# 0152_HPB_BATTERY_CHARGE.net
KiCad netlist of a schematic drawn in Altium Designer
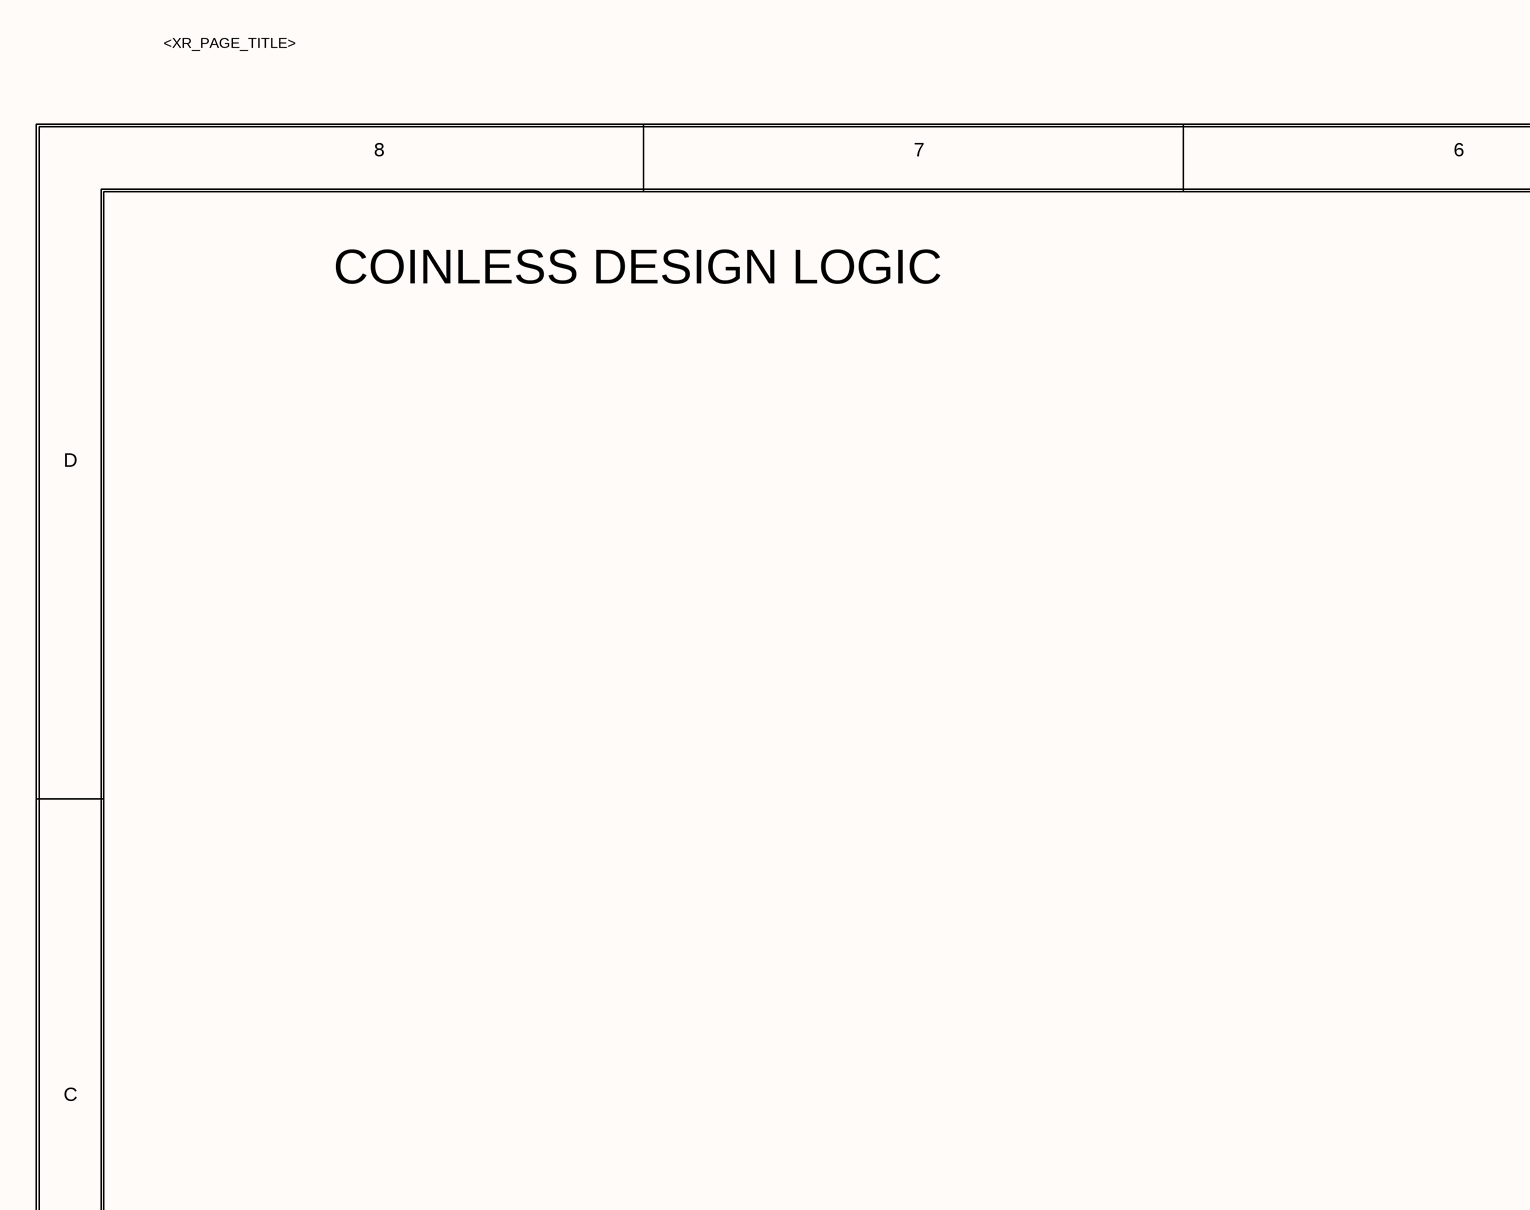
[diagram p0: 0152_HPB BATTERY CHARGE.SchDoc, top left]
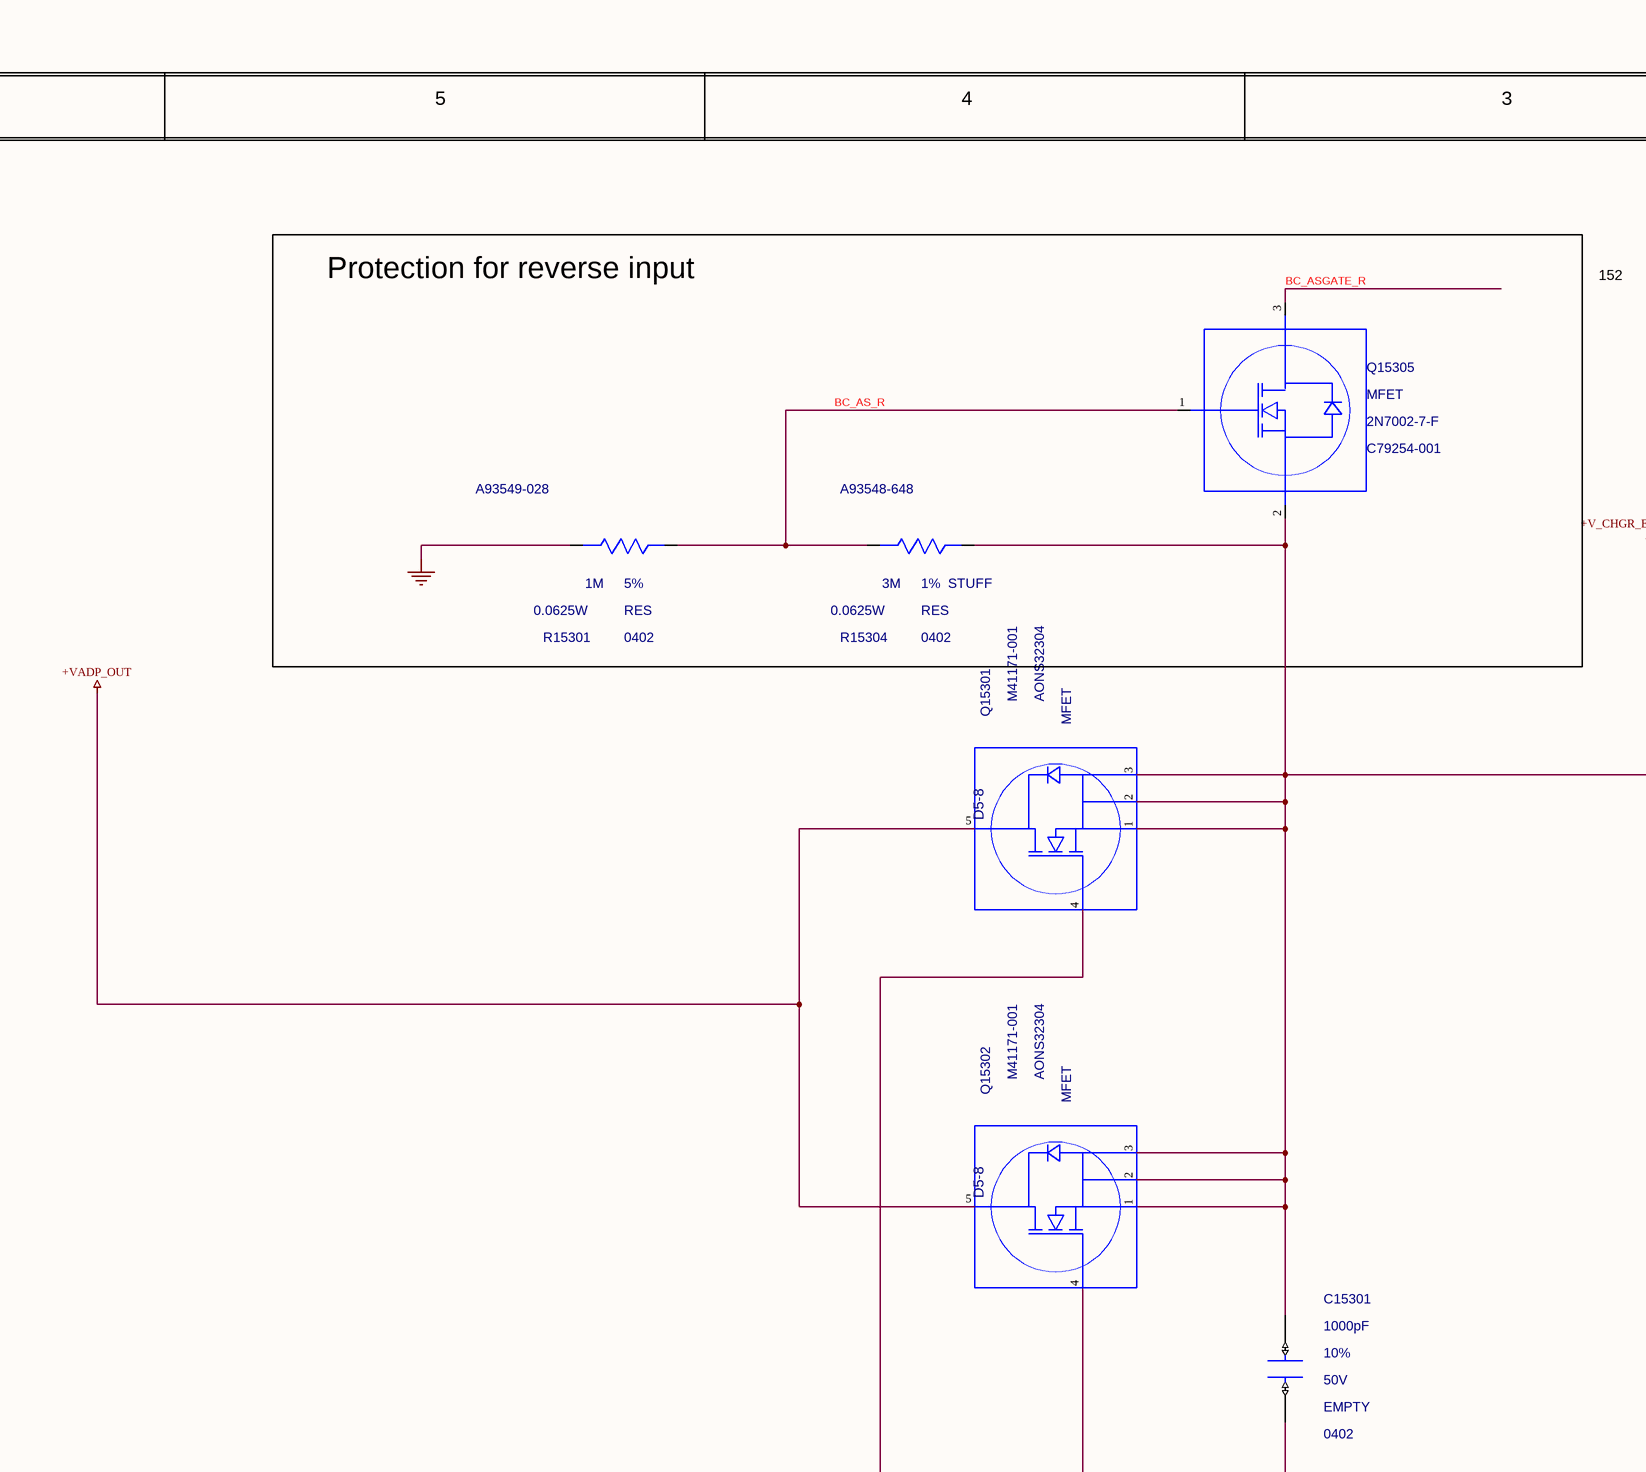
[diagram p1: 0152_HPB BATTERY CHARGE.SchDoc, top middle]
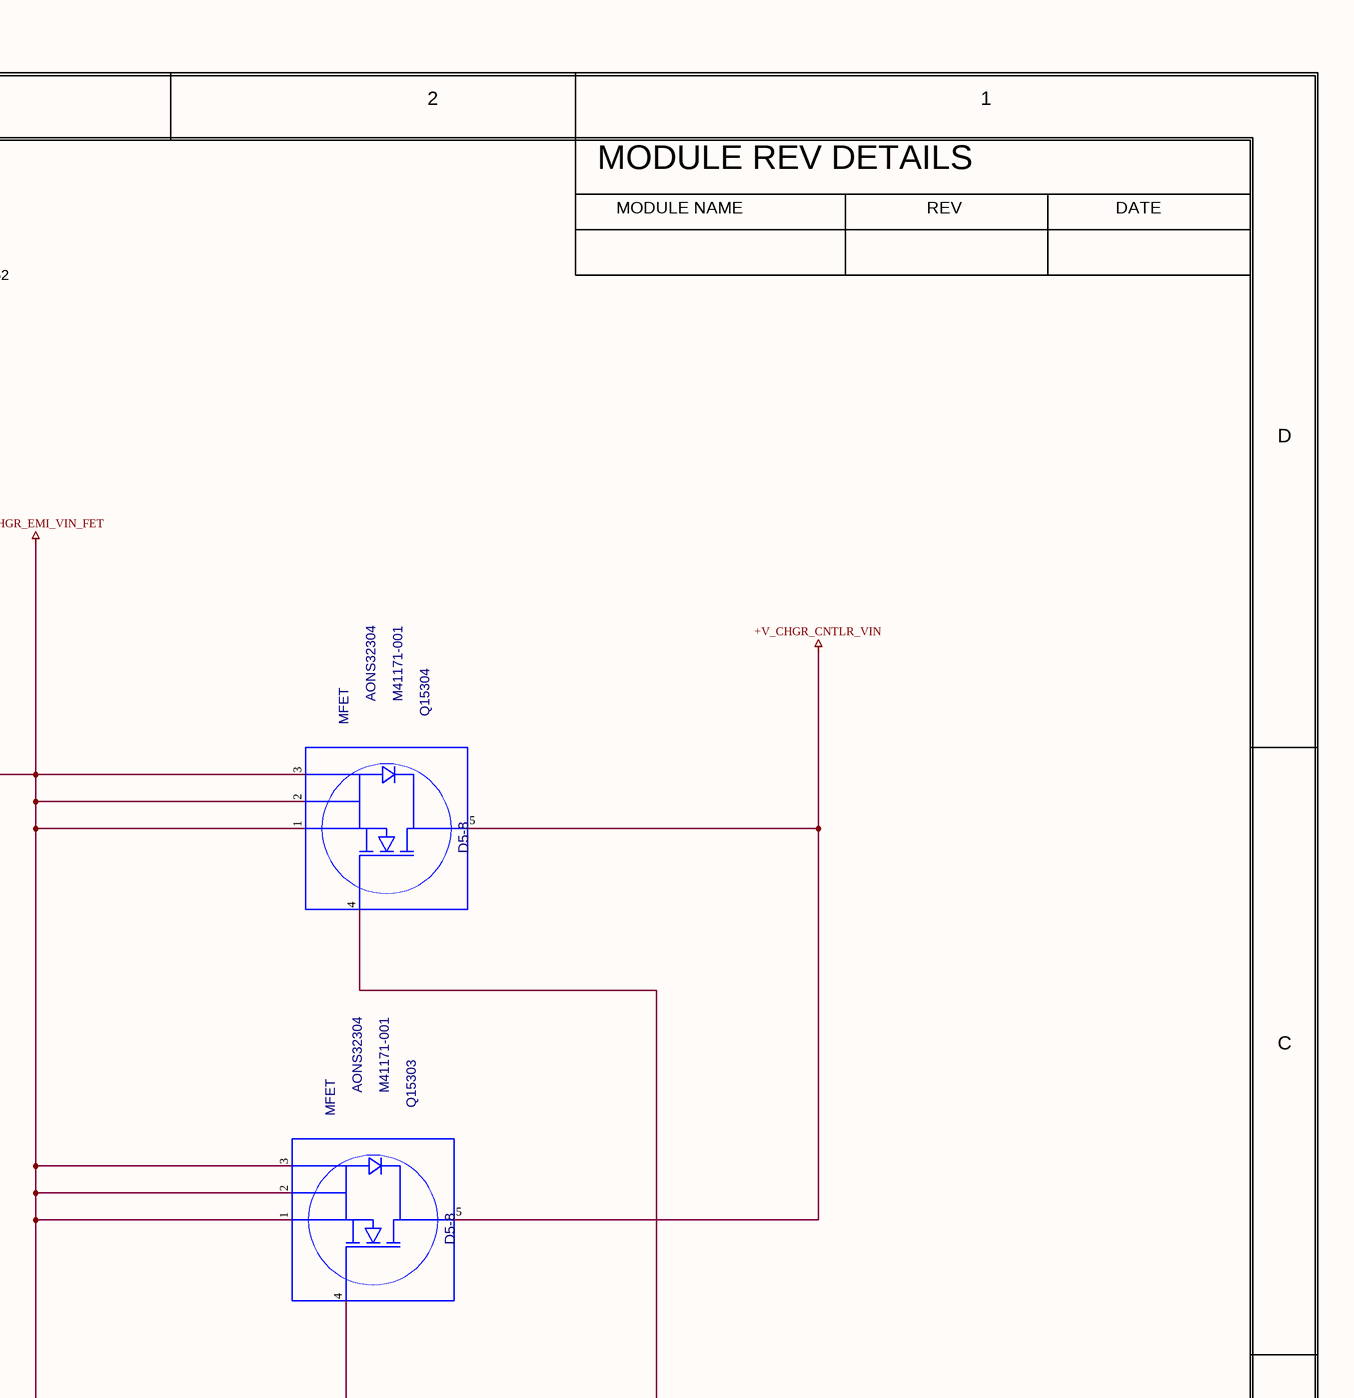
[diagram p2: 0152_HPB BATTERY CHARGE.SchDoc, top right]
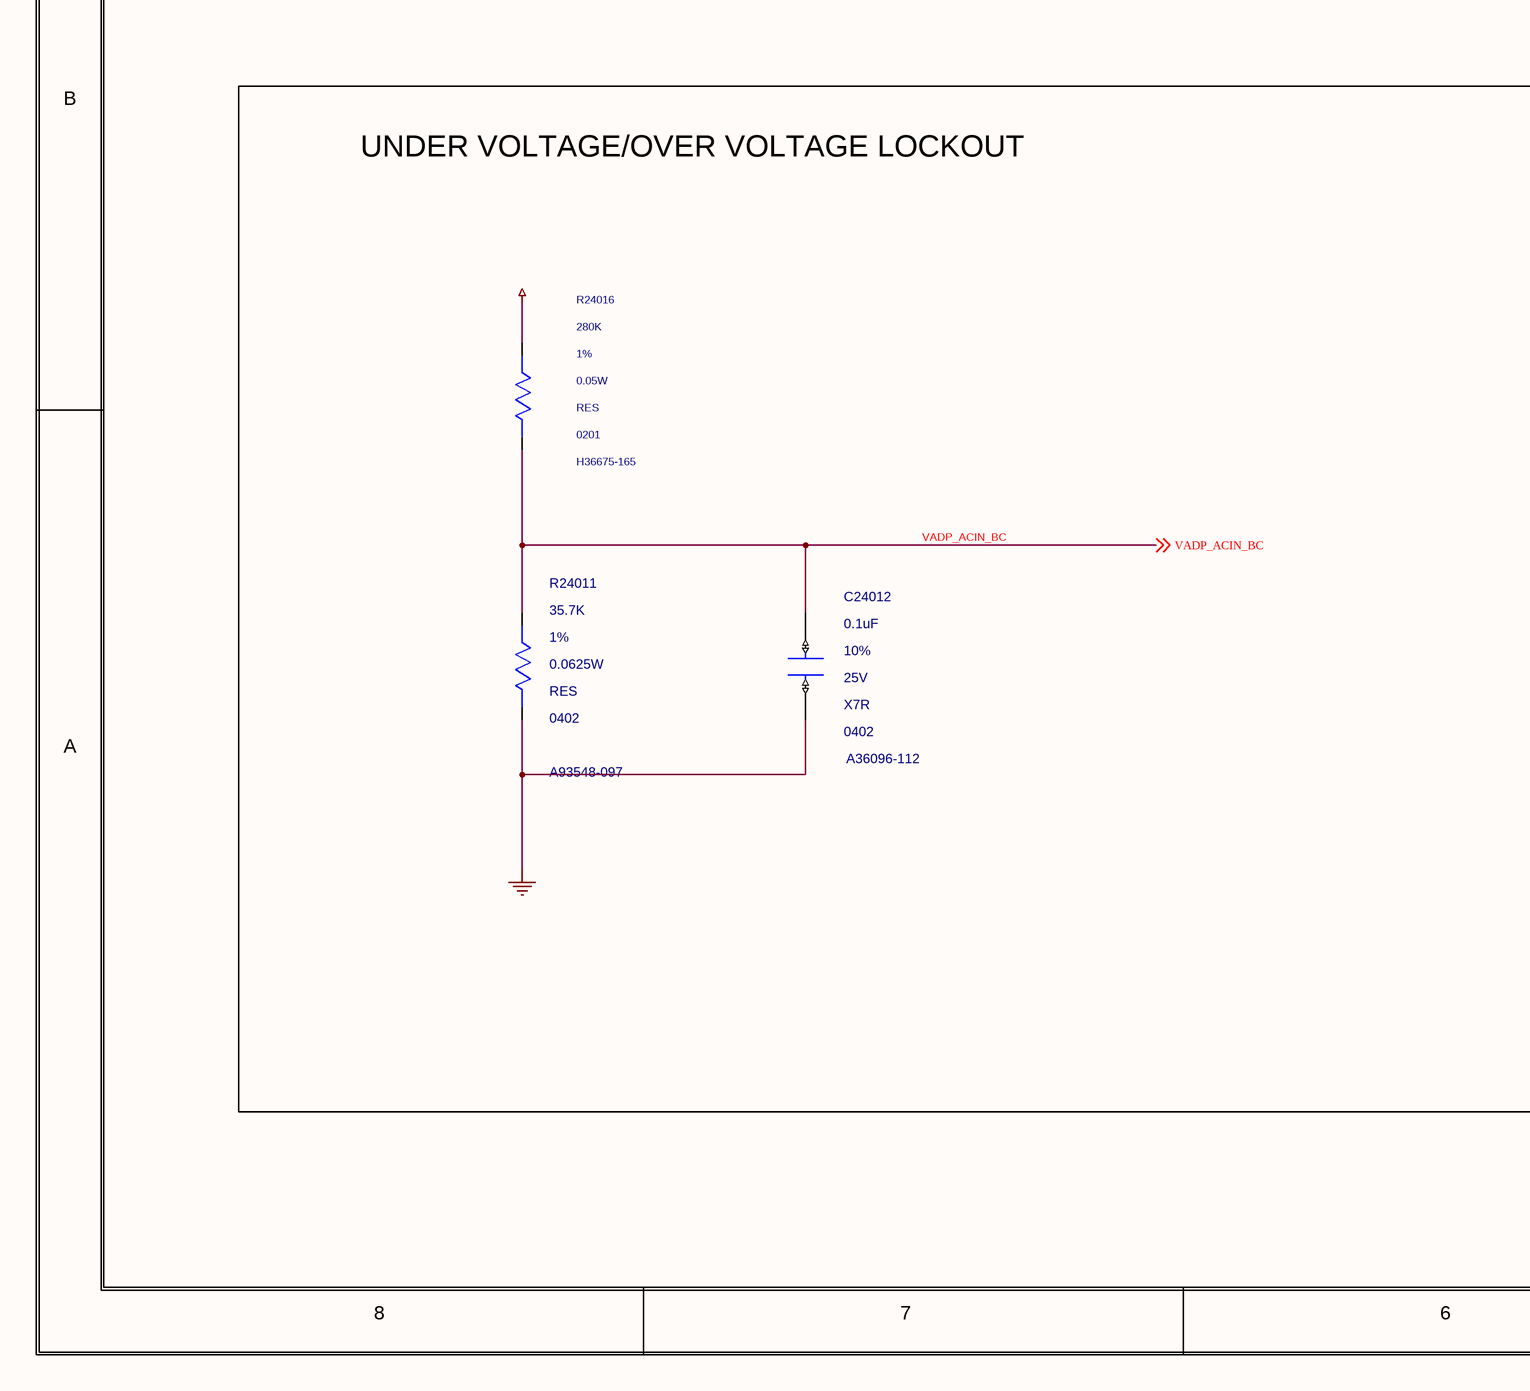
[diagram p3: 0152_HPB BATTERY CHARGE.SchDoc, bottom left]
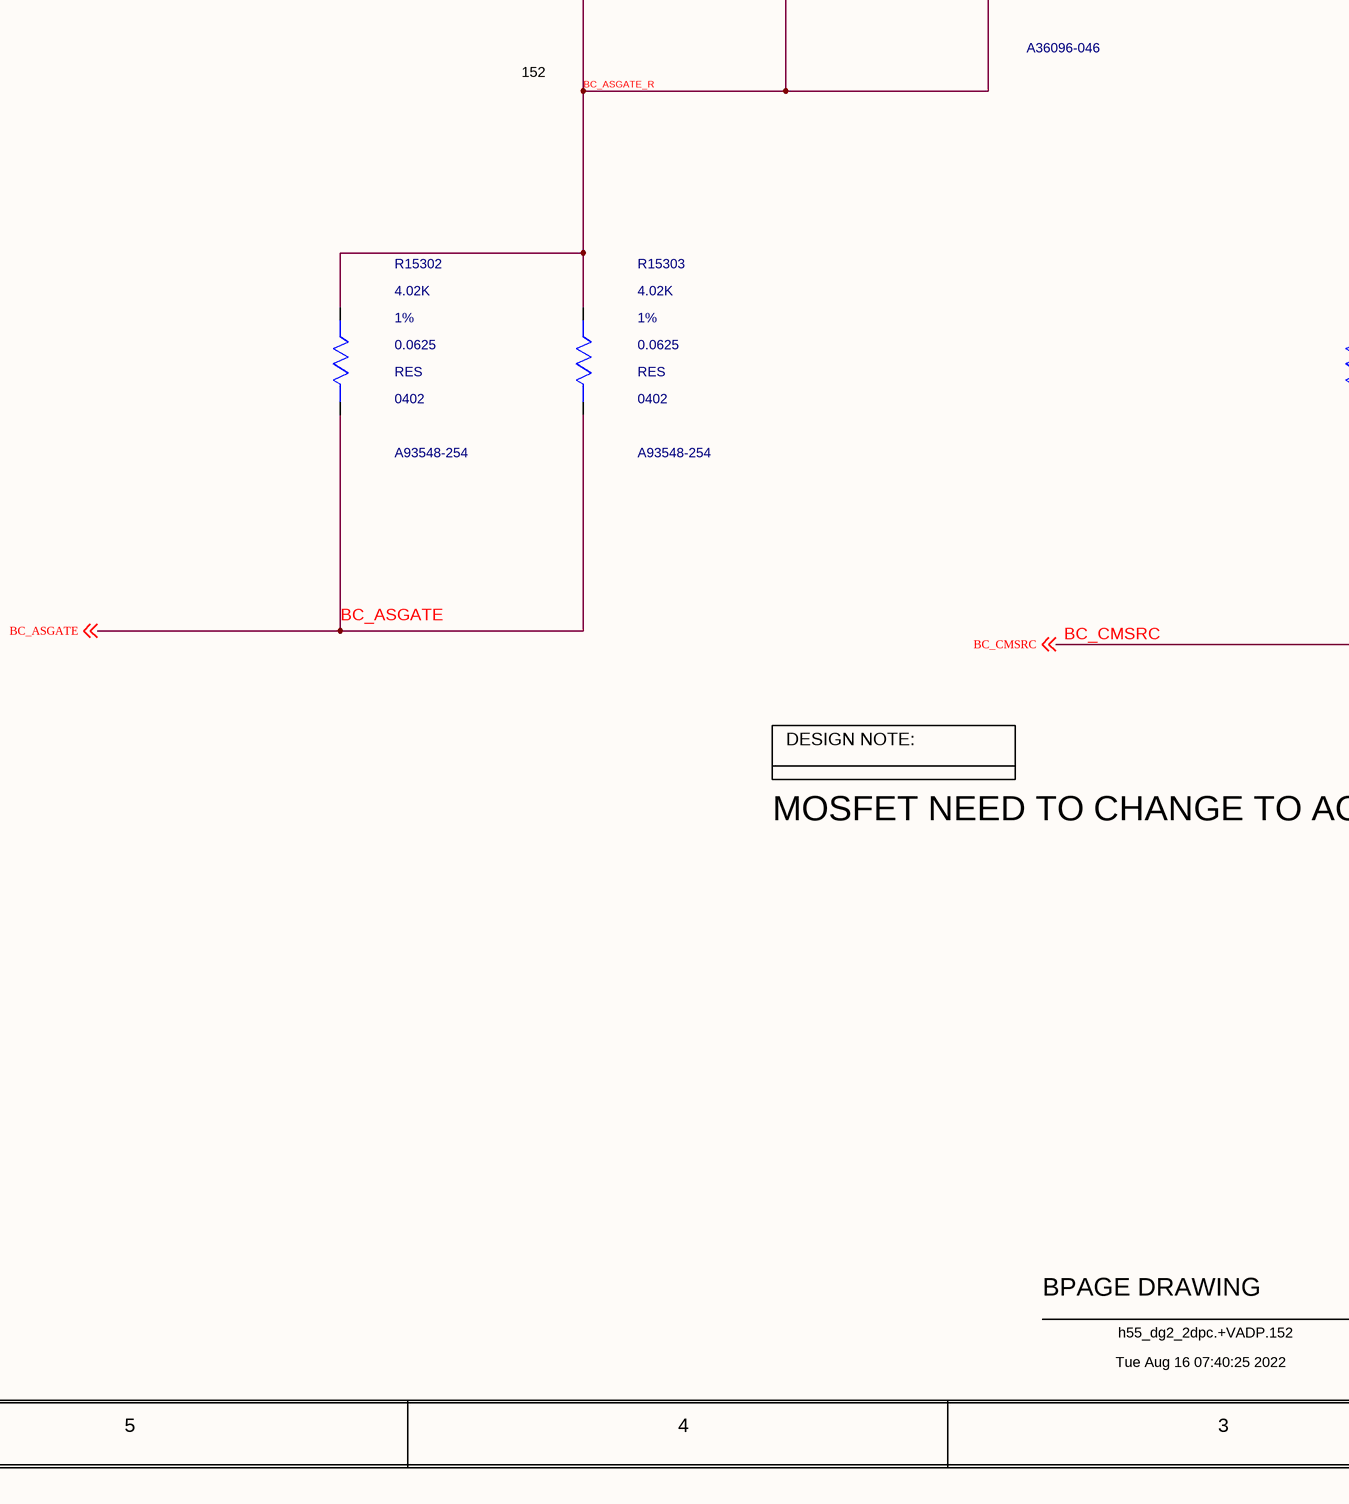
[diagram p4: 0152_HPB BATTERY CHARGE.SchDoc, bottom middle]
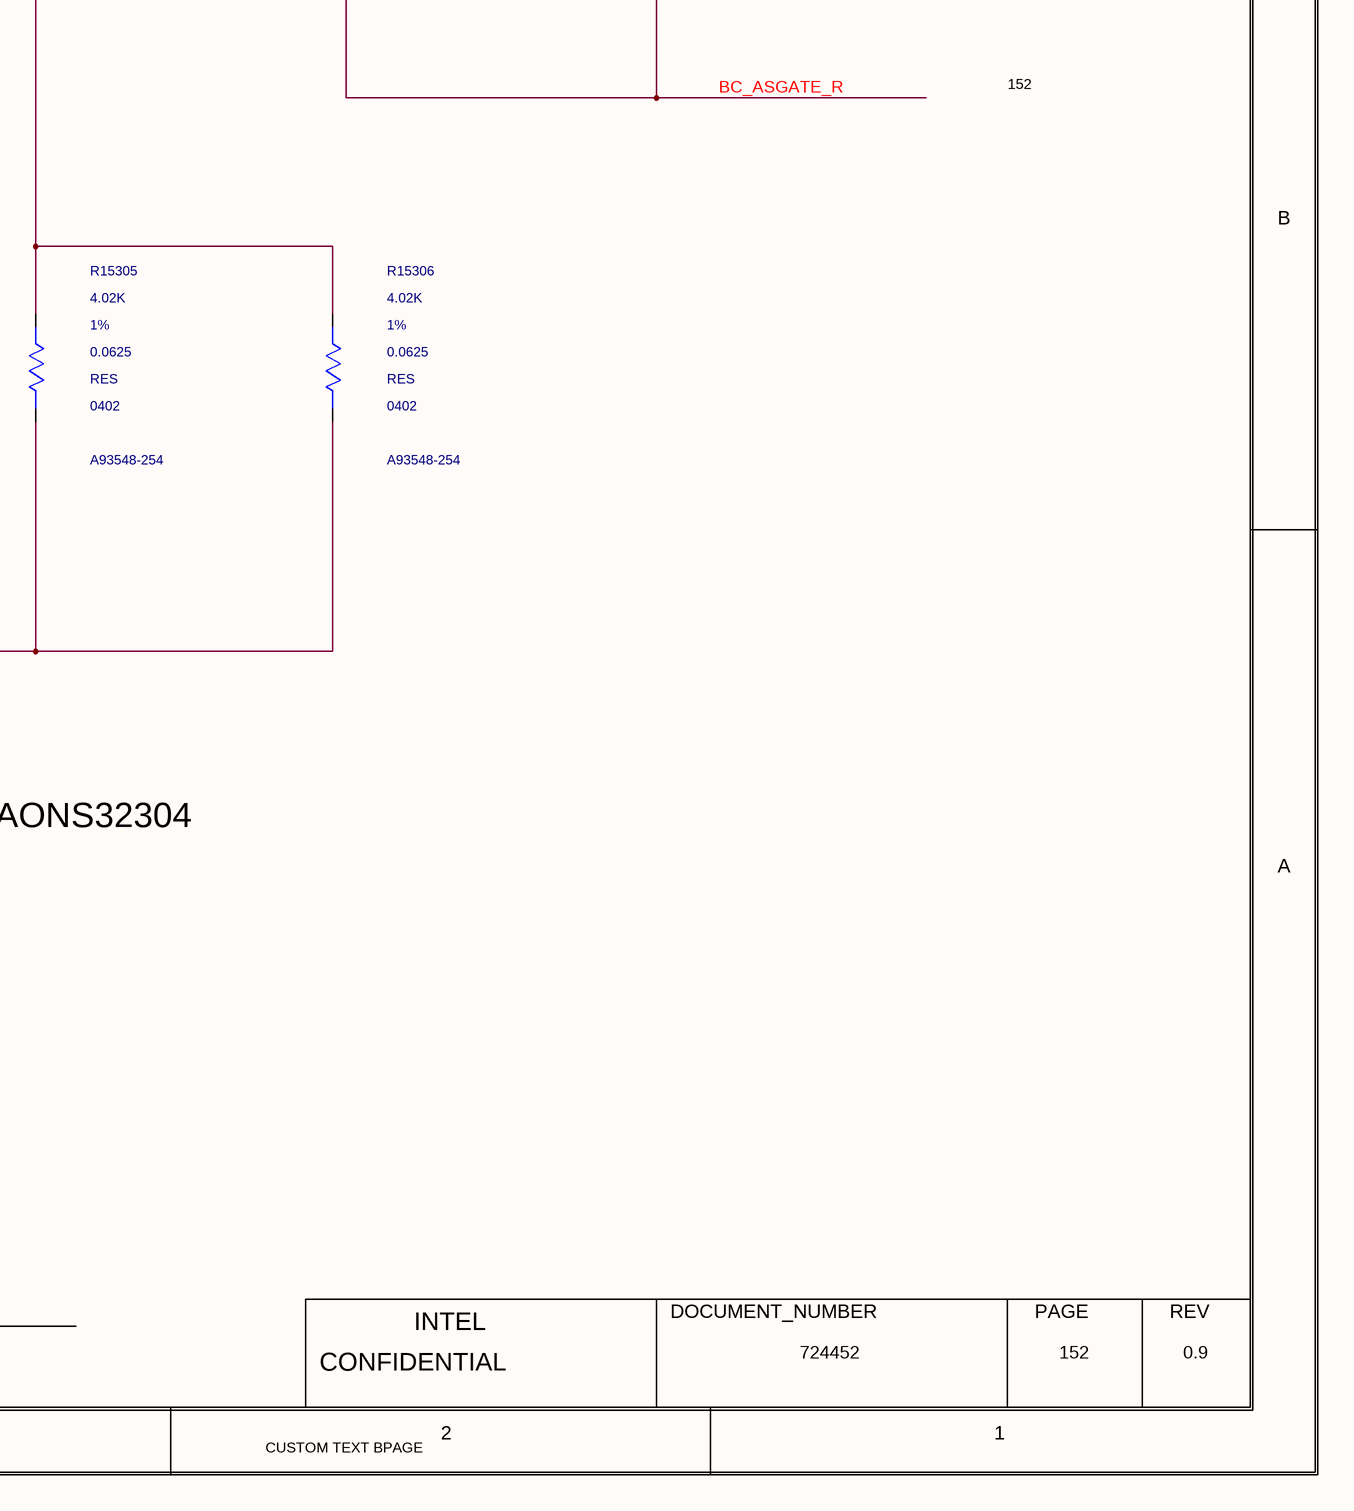
[diagram p5: 0152_HPB BATTERY CHARGE.SchDoc, bottom right]

(export (version "E")
  (design (tool "Eeschema 10.0.6"))
  (components
    (comp (ref "C15301")
      (value "1000pF")
      (footprint "CTK0_SM0402_1100X600_MA")
      (fields
        (field (name "MATERIAL") "EMPTY")
        (field (name "PACK_TYPE") "0402")
        (field (name "PART_NUMBER") "A36096-046")
        (field (name "TOLERANCE") "10%")
        (field (name "VOLTAGE") "50V")
      )
      (libsource (lib "*") (part "C_CAP"))
    )
    (comp (ref "C24012")
      (value "0.1uF")
      (footprint "CTK2_SM0402_1050X550_MA")
      (fields
        (field (name "MATERIAL") "X7R")
        (field (name "PACK_TYPE") "0402")
        (field (name "PART_NUMBER") "A36096-112")
        (field (name "TOLERANCE") "10%")
        (field (name "VOLTAGE") "25V")
      )
      (libsource (lib "*") (part "C_CAP"))
    )
    (comp (ref "Q15301")
      (value "AONS32304")
      (footprint "CTK0_LCC8_5650X5300_1270_DF4670X4600_MA_VR")
      (fields (field (name "MATERIAL") "MFET") (field (name "PART_NUMBER") "M41171-001"))
      (libsource (lib "*") (part "C_MOSFET_N_4D3S1G"))
    )
    (comp (ref "Q15302")
      (value "AONS32304")
      (footprint "CTK0_LCC8_5650X5300_1270_DF4670X4600_MA_VR")
      (fields (field (name "MATERIAL") "MFET") (field (name "PART_NUMBER") "M41171-001"))
      (libsource (lib "*") (part "C_MOSFET_N_4D3S1G"))
    )
    (comp (ref "Q15303")
      (value "AONS32304")
      (footprint "CTK0_LCC8_5650X5300_1270_DF4670X4600_MA_VR")
      (fields (field (name "MATERIAL") "MFET") (field (name "PART_NUMBER") "M41171-001"))
      (libsource (lib "*") (part "C_MOSFET_N_4D3S1G"))
    )
    (comp (ref "Q15304")
      (value "AONS32304")
      (footprint "CTK0_LCC8_5650X5300_1270_DF4670X4600_MA_VR")
      (fields (field (name "MATERIAL") "MFET") (field (name "PART_NUMBER") "M41171-001"))
      (libsource (lib "*") (part "C_MOSFET_N_4D3S1G"))
    )
    (comp (ref "Q15305")
      (value "2N7002-7-F")
      (footprint "CTK0_SOT23_1400X3040_950_MG")
      (fields (field (name "MATERIAL") "MFET") (field (name "PART_NUMBER") "C79254-001"))
      (libsource (lib "*") (part "C_MOSFET_N#1"))
    )
    (comp (ref "R15301")
      (value "1M")
      (footprint "CTK0_SM0402_1100X550_MA")
      (fields
        (field (name "MATERIAL") "RES")
        (field (name "PACK_TYPE") "0402")
        (field (name "PART_NUMBER") "A93549-028")
        (field (name "TOLERANCE") "5%")
        (field (name "WATTAGE") "0.0625W")
      )
      (libsource (lib "*") (part "C_RES#1"))
    )
    (comp (ref "R15302")
      (value "4.02K")
      (footprint "CTK0_SM0402_1100X550_MA")
      (fields
        (field (name "MATERIAL") "RES")
        (field (name "PACK_TYPE") "0402")
        (field (name "PART_NUMBER") "A93548-254")
        (field (name "TOLERANCE") "1%")
        (field (name "WATTAGE") "0.0625")
      )
      (libsource (lib "*") (part "C_RES"))
    )
    (comp (ref "R15303")
      (value "4.02K")
      (footprint "CTK0_SM0402_1100X550_MA")
      (fields
        (field (name "MATERIAL") "RES")
        (field (name "PACK_TYPE") "0402")
        (field (name "PART_NUMBER") "A93548-254")
        (field (name "TOLERANCE") "1%")
        (field (name "WATTAGE") "0.0625")
      )
      (libsource (lib "*") (part "C_RES"))
    )
    (comp (ref "R15304")
      (value "3M")
      (footprint "TK0_SM0402_1100X550_MG")
      (fields
        (field (name "BOM_USE") "STUFF")
        (field (name "MATERIAL") "RES")
        (field (name "PACK_TYPE") "0402")
        (field (name "PART_NUMBER") "A93548-648")
        (field (name "TOLERANCE") "1%")
        (field (name "WATTAGE") "0.0625W")
      )
      (libsource (lib "*") (part "RES_2#1"))
    )
    (comp (ref "R15305")
      (value "4.02K")
      (footprint "CTK0_SM0402_1100X550_MA")
      (fields
        (field (name "MATERIAL") "RES")
        (field (name "PACK_TYPE") "0402")
        (field (name "PART_NUMBER") "A93548-254")
        (field (name "TOLERANCE") "1%")
        (field (name "WATTAGE") "0.0625")
      )
      (libsource (lib "*") (part "C_RES"))
    )
    (comp (ref "R15306")
      (value "4.02K")
      (footprint "CTK0_SM0402_1100X550_MA")
      (fields
        (field (name "MATERIAL") "RES")
        (field (name "PACK_TYPE") "0402")
        (field (name "PART_NUMBER") "A93548-254")
        (field (name "TOLERANCE") "1%")
        (field (name "WATTAGE") "0.0625")
      )
      (libsource (lib "*") (part "C_RES"))
    )
    (comp (ref "R24011")
      (value "35.7K")
      (footprint "CTK0_SM0402_1100X550_MA")
      (fields
        (field (name "MATERIAL") "RES")
        (field (name "PACK_TYPE") "0402")
        (field (name "PART_NUMBER") "A93548-097")
        (field (name "TOLERANCE") "1%")
        (field (name "WATTAGE") "0.0625W")
      )
      (libsource (lib "*") (part "C_RES"))
    )
    (comp (ref "R24016")
      (value "280K")
      (footprint "CTK0_SM0201_630X330_MA")
      (fields
        (field (name "MATERIAL") "RES")
        (field (name "PACK_TYPE") "0201")
        (field (name "PART_NUMBER") "H36675-165")
        (field (name "TOLERANCE") "1%")
        (field (name "WATTAGE") "0.05W")
      )
      (libsource (lib "*") (part "C_RES"))
    )
  )
  (nets
    (net (code "1") (name "+VADP_OUT") (class "Default")
      (node (ref "Q15301") (pin "5") (pinfunction "D_5") (pintype "bidirectional"))
      (node (ref "Q15302") (pin "5") (pinfunction "D_5") (pintype "bidirectional"))
      (node (ref "R24016") (pin "1") (pinfunction "A_1") (pintype "bidirectional"))
    )
    (net (code "2") (name "+V_CHGR_CNTLR_VIN") (class "Default")
      (node (ref "Q15303") (pin "5") (pinfunction "D_5") (pintype "bidirectional"))
      (node (ref "Q15304") (pin "5") (pinfunction "D_5") (pintype "bidirectional"))
    )
    (net (code "3") (name "+V_CHGR_EMI_VIN_FET") (class "Default")
      (node (ref "C15301") (pin "1") (pinfunction "A_1") (pintype "bidirectional"))
      (node (ref "Q15301") (pin "1") (pinfunction "S1_1") (pintype "bidirectional"))
      (node (ref "Q15301") (pin "2") (pinfunction "S2_2") (pintype "bidirectional"))
      (node (ref "Q15301") (pin "3") (pinfunction "S3_3") (pintype "bidirectional"))
      (node (ref "Q15302") (pin "1") (pinfunction "S1_1") (pintype "bidirectional"))
      (node (ref "Q15302") (pin "2") (pinfunction "S2_2") (pintype "bidirectional"))
      (node (ref "Q15302") (pin "3") (pinfunction "S3_3") (pintype "bidirectional"))
      (node (ref "Q15303") (pin "1") (pinfunction "S1_1") (pintype "bidirectional"))
      (node (ref "Q15303") (pin "2") (pinfunction "S2_2") (pintype "bidirectional"))
      (node (ref "Q15303") (pin "3") (pinfunction "S3_3") (pintype "bidirectional"))
      (node (ref "Q15304") (pin "1") (pinfunction "S1_1") (pintype "bidirectional"))
      (node (ref "Q15304") (pin "2") (pinfunction "S2_2") (pintype "bidirectional"))
      (node (ref "Q15304") (pin "3") (pinfunction "S3_3") (pintype "bidirectional"))
      (node (ref "Q15305") (pin "2") (pinfunction "S_2") (pintype "bidirectional"))
      (node (ref "R15304") (pin "2") (pinfunction "B_2") (pintype "bidirectional"))
      (node (ref "R15305") (pin "1") (pinfunction "A_1") (pintype "bidirectional"))
      (node (ref "R15306") (pin "1") (pinfunction "A_1") (pintype "bidirectional"))
    )
    (net (code "4") (name "/BC_ASGATE_R") (class "Default")
      (node (ref "C15301") (pin "2") (pinfunction "B_2") (pintype "bidirectional"))
      (node (ref "Q15301") (pin "4") (pinfunction "G_4") (pintype "bidirectional"))
      (node (ref "Q15302") (pin "4") (pinfunction "G_4") (pintype "bidirectional"))
      (node (ref "Q15303") (pin "4") (pinfunction "G_4") (pintype "bidirectional"))
      (node (ref "Q15304") (pin "4") (pinfunction "G_4") (pintype "bidirectional"))
      (node (ref "Q15305") (pin "3") (pinfunction "D_3") (pintype "bidirectional"))
      (node (ref "R15302") (pin "1") (pinfunction "A_1") (pintype "bidirectional"))
      (node (ref "R15303") (pin "1") (pinfunction "A_1") (pintype "bidirectional"))
    )
    (net (code "5") (name "/BC_AS_R") (class "Default")
      (node (ref "Q15305") (pin "1") (pinfunction "G_1") (pintype "bidirectional"))
      (node (ref "R15301") (pin "2") (pinfunction "B_2") (pintype "bidirectional"))
      (node (ref "R15304") (pin "1") (pinfunction "A_1") (pintype "bidirectional"))
    )
    (net (code "6") (name "BC_ASGATE") (class "Default")
      (node (ref "R15302") (pin "2") (pinfunction "B_2") (pintype "bidirectional"))
      (node (ref "R15303") (pin "2") (pinfunction "B_2") (pintype "bidirectional"))
    )
    (net (code "7") (name "BC_CMSRC") (class "Default")
      (node (ref "R15305") (pin "2") (pinfunction "B_2") (pintype "bidirectional"))
      (node (ref "R15306") (pin "2") (pinfunction "B_2") (pintype "bidirectional"))
    )
    (net (code "8") (name "GND") (class "Default")
      (node (ref "C24012") (pin "2") (pinfunction "B_2") (pintype "bidirectional"))
      (node (ref "R15301") (pin "1") (pinfunction "A_1") (pintype "bidirectional"))
      (node (ref "R24011") (pin "2") (pinfunction "B_2") (pintype "bidirectional"))
    )
    (net (code "9") (name "VADP_ACIN_BC") (class "Default")
      (node (ref "C24012") (pin "1") (pinfunction "A_1") (pintype "bidirectional"))
      (node (ref "R24011") (pin "1") (pinfunction "A_1") (pintype "bidirectional"))
      (node (ref "R24016") (pin "2") (pinfunction "B_2") (pintype "bidirectional"))
    )
  )
)
